# ESP32.net
KiCad netlist of a schematic drawn in Altium Designer
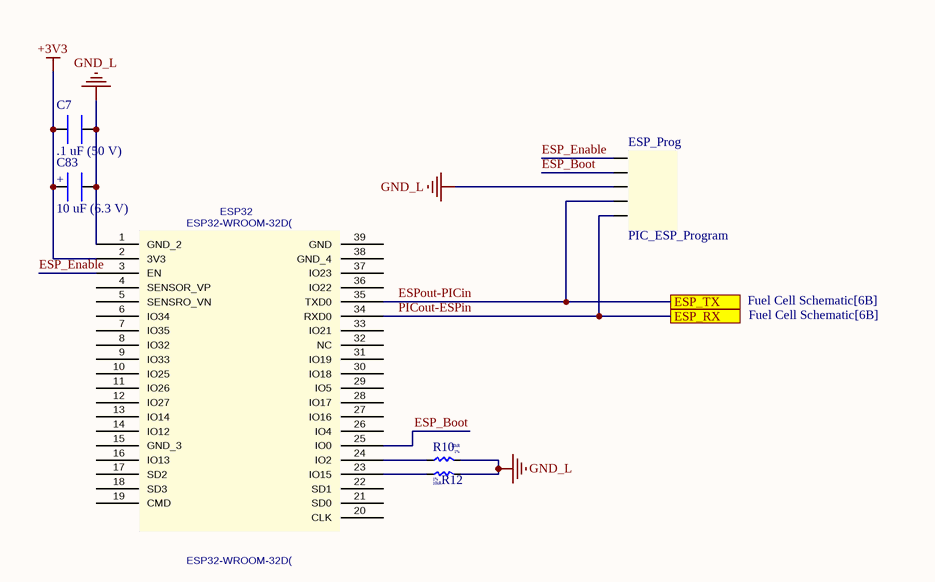
[diagram p0: ESP32.SchDoc]

(export (version "E")
  (design (tool "Eeschema 10.0.6"))
  (components
    (comp (ref "C7")
      (value ".1 uF (50 V)")
      (footprint ".1uF capacitor")
      (libsource (lib "Schlib1") (part ".1 uF cap"))
    )
    (comp (ref "C83")
      (value "10 uF (6.3 V)")
      (footprint "10 uF cap")
      (libsource (lib "Schlib1") (part "10 uF cap"))
    )
    (comp (ref "ESP32")
      (value "ESP32-WROOM-32D(")
      (footprint "ESP32")
      (fields
        (field (name "MANUFACTURER_PART_NUMBER") "ESP32-WROOM-32D(M113DH6400PH3Q0)")
        (field (name "ALTIUM_VALUE") "ESP32-WROOM-32D(")
        (field (name "COPYRIGHT") "Copyright (C) 2023 Ultra Librarian. All rights reserved.")
      )
      (libsource (lib "Schlib1") (part "ESP32-WROOM-32D("))
    )
    (comp (ref "ESP_Prog")
      (value "PIC_ESP_Program")
      (footprint "ESP_Program")
      (libsource (lib "Schlib1") (part "PIC_ESP_Program"))
    )
    (comp (ref "R10")
      (value "~")
      (footprint "Resistor_YAGEO_0805")
      (description "RES 10K OHM 1% 1/8W 0805")
      (fields
        (field (name "MANUFACTURER") "Yageo")
        (field (name "MANUFACTURER PART NUMBER") "RC0805FR-1010KL")
        (field (name "TOLERANCE") "1%")
        (field (name "RESISTANCE") "10kR")
      )
      (libsource (lib "Schlib1") (part "RC0805FR-1010KL"))
    )
    (comp (ref "R12")
      (value "~")
      (footprint "Resistor_YAGEO_0805")
      (description "RES 10K OHM 1% 1/8W 0805")
      (fields
        (field (name "MANUFACTURER") "Yageo")
        (field (name "MANUFACTURER PART NUMBER") "RC0805FR-1010KL")
        (field (name "TOLERANCE") "1%")
        (field (name "RESISTANCE") "10kR")
      )
      (libsource (lib "Schlib1") (part "RC0805FR-1010KL"))
    )
  )
  (nets
    (net (code "1") (name "+3V3") (class "Default")
      (node (ref "C7") (pin "1") (pinfunction "1_1") (pintype "passive"))
      (node (ref "C83") (pin "1") (pinfunction "1_1") (pintype "passive"))
      (node (ref "ESP32") (pin "2") (pinfunction "3V3_2") (pintype "passive"))
    )
    (net (code "2") (name "/ESP_Boot") (class "Default")
      (node (ref "ESP32") (pin "25") (pinfunction "IO0_25") (pintype "passive"))
      (node (ref "ESP_Prog") (pin "4") (pinfunction "Boot_4") (pintype "passive"))
    )
    (net (code "3") (name "/ESP_Enable") (class "Default")
      (node (ref "ESP32") (pin "3") (pinfunction "EN_3") (pintype "passive"))
      (node (ref "ESP_Prog") (pin "5") (pinfunction "Enable_5") (pintype "passive"))
    )
    (net (code "4") (name "/ESPout-PICin") (class "Default")
      (node (ref "ESP32") (pin "35") (pinfunction "TXD0_35") (pintype "passive"))
      (node (ref "ESP_Prog") (pin "2") (pinfunction "RX_2") (pintype "passive"))
    )
    (net (code "5") (name "/PICout-ESPin") (class "Default")
      (node (ref "ESP32") (pin "34") (pinfunction "RXD0_34") (pintype "passive"))
      (node (ref "ESP_Prog") (pin "1") (pinfunction "TX_1") (pintype "passive"))
    )
    (net (code "6") (name "GND_L") (class "Default")
      (node (ref "C7") (pin "2") (pinfunction "2_2") (pintype "passive"))
      (node (ref "C83") (pin "2") (pinfunction "2_2") (pintype "passive"))
      (node (ref "ESP32") (pin "1") (pinfunction "GND_2_1") (pintype "passive"))
      (node (ref "ESP_Prog") (pin "3") (pinfunction "GND_3") (pintype "passive"))
      (node (ref "R10") (pin "2") (pinfunction "2_2") (pintype "passive"))
      (node (ref "R12") (pin "2") (pinfunction "2_2") (pintype "passive"))
    )
    (net (code "7") (name "Net-(ESP32-IO2)") (class "Default")
      (node (ref "ESP32") (pin "24") (pinfunction "IO2_24") (pintype "passive"))
      (node (ref "R10") (pin "1") (pinfunction "1_1") (pintype "passive"))
    )
    (net (code "8") (name "Net-(ESP32-IO15)") (class "Default")
      (node (ref "ESP32") (pin "23") (pinfunction "IO15_23") (pintype "passive"))
      (node (ref "R12") (pin "1") (pinfunction "1_1") (pintype "passive"))
    )
    (net (code "9") (name "unconnected-(ESP32-CLK-Pad20)") (class "Default")
      (node (ref "ESP32") (pin "20") (pinfunction "CLK_20") (pintype "passive"))
    )
    (net (code "10") (name "unconnected-(ESP32-CMD-Pad19)") (class "Default")
      (node (ref "ESP32") (pin "19") (pinfunction "CMD_19") (pintype "passive"))
    )
    (net (code "11") (name "unconnected-(ESP32-GND-Pad39)") (class "Default")
      (node (ref "ESP32") (pin "39") (pinfunction "GND_39") (pintype "passive"))
    )
    (net (code "12") (name "unconnected-(ESP32-GND_3-Pad15)") (class "Default")
      (node (ref "ESP32") (pin "15") (pinfunction "GND_3_15") (pintype "passive"))
    )
    (net (code "13") (name "unconnected-(ESP32-GND_4-Pad38)") (class "Default")
      (node (ref "ESP32") (pin "38") (pinfunction "GND_4_38") (pintype "passive"))
    )
    (net (code "14") (name "unconnected-(ESP32-IO4-Pad26)") (class "Default")
      (node (ref "ESP32") (pin "26") (pinfunction "IO4_26") (pintype "passive"))
    )
    (net (code "15") (name "unconnected-(ESP32-IO5-Pad29)") (class "Default")
      (node (ref "ESP32") (pin "29") (pinfunction "IO5_29") (pintype "passive"))
    )
    (net (code "16") (name "unconnected-(ESP32-IO12-Pad14)") (class "Default")
      (node (ref "ESP32") (pin "14") (pinfunction "IO12_14") (pintype "passive"))
    )
    (net (code "17") (name "unconnected-(ESP32-IO13-Pad16)") (class "Default")
      (node (ref "ESP32") (pin "16") (pinfunction "IO13_16") (pintype "passive"))
    )
    (net (code "18") (name "unconnected-(ESP32-IO14-Pad13)") (class "Default")
      (node (ref "ESP32") (pin "13") (pinfunction "IO14_13") (pintype "passive"))
    )
    (net (code "19") (name "unconnected-(ESP32-IO16-Pad27)") (class "Default")
      (node (ref "ESP32") (pin "27") (pinfunction "IO16_27") (pintype "passive"))
    )
    (net (code "20") (name "unconnected-(ESP32-IO17-Pad28)") (class "Default")
      (node (ref "ESP32") (pin "28") (pinfunction "IO17_28") (pintype "passive"))
    )
    (net (code "21") (name "unconnected-(ESP32-IO18-Pad30)") (class "Default")
      (node (ref "ESP32") (pin "30") (pinfunction "IO18_30") (pintype "passive"))
    )
    (net (code "22") (name "unconnected-(ESP32-IO19-Pad31)") (class "Default")
      (node (ref "ESP32") (pin "31") (pinfunction "IO19_31") (pintype "passive"))
    )
    (net (code "23") (name "unconnected-(ESP32-IO21-Pad33)") (class "Default")
      (node (ref "ESP32") (pin "33") (pinfunction "IO21_33") (pintype "passive"))
    )
    (net (code "24") (name "unconnected-(ESP32-IO22-Pad36)") (class "Default")
      (node (ref "ESP32") (pin "36") (pinfunction "IO22_36") (pintype "passive"))
    )
    (net (code "25") (name "unconnected-(ESP32-IO23-Pad37)") (class "Default")
      (node (ref "ESP32") (pin "37") (pinfunction "IO23_37") (pintype "passive"))
    )
    (net (code "26") (name "unconnected-(ESP32-IO25-Pad10)") (class "Default")
      (node (ref "ESP32") (pin "10") (pinfunction "IO25_10") (pintype "passive"))
    )
    (net (code "27") (name "unconnected-(ESP32-IO26-Pad11)") (class "Default")
      (node (ref "ESP32") (pin "11") (pinfunction "IO26_11") (pintype "passive"))
    )
    (net (code "28") (name "unconnected-(ESP32-IO27-Pad12)") (class "Default")
      (node (ref "ESP32") (pin "12") (pinfunction "IO27_12") (pintype "passive"))
    )
    (net (code "29") (name "unconnected-(ESP32-IO32-Pad8)") (class "Default")
      (node (ref "ESP32") (pin "8") (pinfunction "IO32_8") (pintype "passive"))
    )
    (net (code "30") (name "unconnected-(ESP32-IO33-Pad9)") (class "Default")
      (node (ref "ESP32") (pin "9") (pinfunction "IO33_9") (pintype "passive"))
    )
    (net (code "31") (name "unconnected-(ESP32-IO34-Pad6)") (class "Default")
      (node (ref "ESP32") (pin "6") (pinfunction "IO34_6") (pintype "passive"))
    )
    (net (code "32") (name "unconnected-(ESP32-IO35-Pad7)") (class "Default")
      (node (ref "ESP32") (pin "7") (pinfunction "IO35_7") (pintype "passive"))
    )
    (net (code "33") (name "unconnected-(ESP32-NC-Pad32)") (class "Default")
      (node (ref "ESP32") (pin "32") (pinfunction "NC_32") (pintype "passive"))
    )
    (net (code "34") (name "unconnected-(ESP32-SD0-Pad21)") (class "Default")
      (node (ref "ESP32") (pin "21") (pinfunction "SD0_21") (pintype "passive"))
    )
    (net (code "35") (name "unconnected-(ESP32-SD1-Pad22)") (class "Default")
      (node (ref "ESP32") (pin "22") (pinfunction "SD1_22") (pintype "passive"))
    )
    (net (code "36") (name "unconnected-(ESP32-SD2-Pad17)") (class "Default")
      (node (ref "ESP32") (pin "17") (pinfunction "SD2_17") (pintype "passive"))
    )
    (net (code "37") (name "unconnected-(ESP32-SD3-Pad18)") (class "Default")
      (node (ref "ESP32") (pin "18") (pinfunction "SD3_18") (pintype "passive"))
    )
    (net (code "38") (name "unconnected-(ESP32-SENSOR_VP-Pad4)") (class "Default")
      (node (ref "ESP32") (pin "4") (pinfunction "SENSOR_VP_4") (pintype "passive"))
    )
    (net (code "39") (name "unconnected-(ESP32-SENSRO_VN-Pad5)") (class "Default")
      (node (ref "ESP32") (pin "5") (pinfunction "SENSRO_VN_5") (pintype "passive"))
    )
  )
)
